# MessVerstaerker.net
KiCad netlist of a schematic drawn in EAGLE
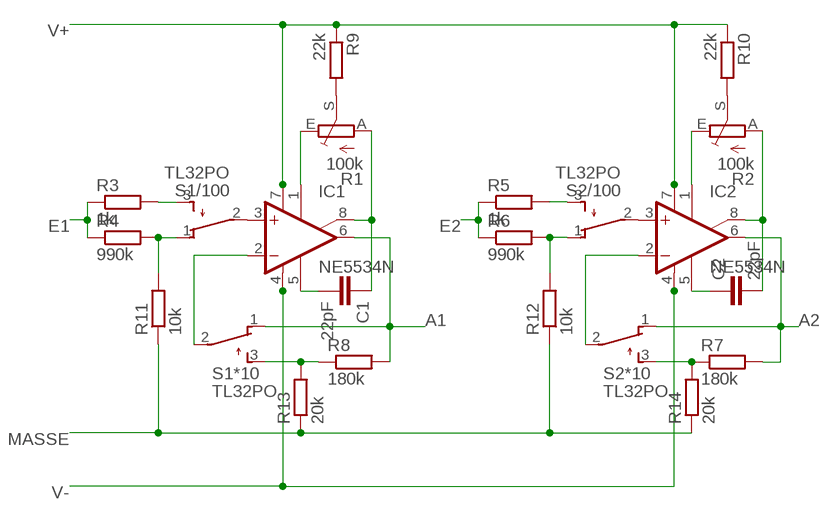
[diagram p0: schematic, sheet 1]

(export (version "E")
  (design (tool "Eeschema 10.0.6"))
  (components
    (comp (ref "C1")
      (value "22pF")
      (footprint "eagle-import:C2.5-2")
      (libsource (lib "eagle-import") (part "C2.5/2"))
    )
    (comp (ref "C2")
      (value "22pF")
      (footprint "eagle-import:C2.5-2")
      (libsource (lib "eagle-import") (part "C2.5/2"))
    )
    (comp (ref "IC1")
      (value "NE5534N")
      (footprint "eagle-import:DIL08")
      (libsource (lib "eagle-import") (part "NE5534N"))
    )
    (comp (ref "IC2")
      (value "NE5534N")
      (footprint "eagle-import:DIL08")
      (libsource (lib "eagle-import") (part "NE5534N"))
    )
    (comp (ref "R1")
      (value "100k")
      (footprint "eagle-import:B25V")
      (libsource (lib "eagle-import") (part "TRIM_EU-B25V"))
    )
    (comp (ref "R2")
      (value "100k")
      (footprint "eagle-import:B25V")
      (libsource (lib "eagle-import") (part "TRIM_EU-B25V"))
    )
    (comp (ref "R3")
      (value "1k")
      (footprint "eagle-import:0309_10")
      (libsource (lib "eagle-import") (part "R-EU_0309/10"))
    )
    (comp (ref "R4")
      (value "990k")
      (footprint "eagle-import:0309_10")
      (libsource (lib "eagle-import") (part "R-EU_0309/10"))
    )
    (comp (ref "R5")
      (value "1k")
      (footprint "eagle-import:0309_10")
      (libsource (lib "eagle-import") (part "R-EU_0309/10"))
    )
    (comp (ref "R6")
      (value "990k")
      (footprint "eagle-import:0309_10")
      (libsource (lib "eagle-import") (part "R-EU_0309/10"))
    )
    (comp (ref "R7")
      (value "180k")
      (footprint "eagle-import:0309_10")
      (libsource (lib "eagle-import") (part "R-EU_0309/10"))
    )
    (comp (ref "R8")
      (value "180k")
      (footprint "eagle-import:0309_10")
      (libsource (lib "eagle-import") (part "R-EU_0309/10"))
    )
    (comp (ref "R9")
      (value "22k")
      (footprint "eagle-import:0309_10")
      (libsource (lib "eagle-import") (part "R-EU_0309/10"))
    )
    (comp (ref "R10")
      (value "22k")
      (footprint "eagle-import:0309_10")
      (libsource (lib "eagle-import") (part "R-EU_0309/10"))
    )
    (comp (ref "R11")
      (value "10k")
      (footprint "eagle-import:0309_10")
      (libsource (lib "eagle-import") (part "R-EU_0309/10"))
    )
    (comp (ref "R12")
      (value "10k")
      (footprint "eagle-import:0309_10")
      (libsource (lib "eagle-import") (part "R-EU_0309/10"))
    )
    (comp (ref "R13")
      (value "20k")
      (footprint "eagle-import:0309_10")
      (libsource (lib "eagle-import") (part "R-EU_0309/10"))
    )
    (comp (ref "R14")
      (value "20k")
      (footprint "eagle-import:0309_10")
      (libsource (lib "eagle-import") (part "R-EU_0309/10"))
    )
    (comp (ref "S1*10")
      (value "TL32PO")
      (footprint "eagle-import:TL3XPO")
      (libsource (lib "eagle-import") (part "TL32PO"))
    )
    (comp (ref "S1/100")
      (value "TL32PO")
      (footprint "eagle-import:TL3XPO")
      (libsource (lib "eagle-import") (part "TL32PO"))
    )
    (comp (ref "S2*10")
      (value "TL32PO")
      (footprint "eagle-import:TL3XPO")
      (libsource (lib "eagle-import") (part "TL32PO"))
    )
    (comp (ref "S2/100")
      (value "TL32PO")
      (footprint "eagle-import:TL3XPO")
      (libsource (lib "eagle-import") (part "TL32PO"))
    )
  )
  (nets
    (net (code "1") (name "/A1") (class "Default")
      (node (ref "IC1") (pin "6") (pinfunction "OUT_6") (pintype "output"))
      (node (ref "R8") (pin "2") (pinfunction "2_2") (pintype "passive"))
      (node (ref "S1*10") (pin "1") (pinfunction "O_1") (pintype "passive"))
    )
    (net (code "2") (name "/A2") (class "Default")
      (node (ref "IC2") (pin "6") (pinfunction "OUT_6") (pintype "output"))
      (node (ref "R7") (pin "2") (pinfunction "2_2") (pintype "passive"))
      (node (ref "S2*10") (pin "1") (pinfunction "O_1") (pintype "passive"))
    )
    (net (code "3") (name "/E1") (class "Default")
      (node (ref "R3") (pin "1") (pinfunction "1_1") (pintype "passive"))
      (node (ref "R4") (pin "1") (pinfunction "1_1") (pintype "passive"))
    )
    (net (code "4") (name "/E2") (class "Default")
      (node (ref "R5") (pin "1") (pinfunction "1_1") (pintype "passive"))
      (node (ref "R6") (pin "1") (pinfunction "1_1") (pintype "passive"))
    )
    (net (code "5") (name "/MASSE") (class "Default")
      (node (ref "R11") (pin "1") (pinfunction "1_1") (pintype "passive"))
      (node (ref "R12") (pin "1") (pinfunction "1_1") (pintype "passive"))
      (node (ref "R13") (pin "1") (pinfunction "1_1") (pintype "passive"))
      (node (ref "R14") (pin "1") (pinfunction "1_1") (pintype "passive"))
    )
    (net (code "6") (name "/V+") (class "Default")
      (node (ref "IC1") (pin "7") (pinfunction "V+_7") (pintype "power_in"))
      (node (ref "IC2") (pin "7") (pinfunction "V+_7") (pintype "power_in"))
      (node (ref "R10") (pin "1") (pinfunction "1_1") (pintype "passive"))
      (node (ref "R9") (pin "1") (pinfunction "1_1") (pintype "passive"))
    )
    (net (code "7") (name "/V-") (class "Default")
      (node (ref "IC1") (pin "4") (pinfunction "V-_4") (pintype "power_in"))
      (node (ref "IC2") (pin "4") (pinfunction "V-_4") (pintype "power_in"))
    )
    (net (code "8") (name "Net-(IC1-+IN)") (class "Default")
      (node (ref "IC1") (pin "3") (pinfunction "+IN_3") (pintype "input"))
      (node (ref "S1/100") (pin "2") (pinfunction "P_2") (pintype "passive"))
    )
    (net (code "9") (name "Net-(IC1--IN)") (class "Default")
      (node (ref "IC1") (pin "2") (pinfunction "-IN_2") (pintype "input"))
      (node (ref "S1*10") (pin "2") (pinfunction "P_2") (pintype "passive"))
    )
    (net (code "10") (name "Net-(IC1-CMP)") (class "Default")
      (node (ref "C1") (pin "2") (pinfunction "2_2") (pintype "passive"))
      (node (ref "IC1") (pin "5") (pinfunction "CMP_5") (pintype "passive"))
    )
    (net (code "11") (name "Net-(IC1-ON)") (class "Default")
      (node (ref "IC1") (pin "1") (pinfunction "ON_1") (pintype "passive"))
      (node (ref "R1") (pin "E") (pinfunction "E_E") (pintype "passive"))
    )
    (net (code "12") (name "Net-(IC1-ON{slash}CMP)") (class "Default")
      (node (ref "C1") (pin "1") (pinfunction "1_1") (pintype "passive"))
      (node (ref "IC1") (pin "8") (pinfunction "ON/CMP_8") (pintype "passive"))
      (node (ref "R1") (pin "A") (pinfunction "A_A") (pintype "passive"))
    )
    (net (code "13") (name "Net-(IC2-+IN)") (class "Default")
      (node (ref "IC2") (pin "3") (pinfunction "+IN_3") (pintype "input"))
      (node (ref "S2/100") (pin "2") (pinfunction "P_2") (pintype "passive"))
    )
    (net (code "14") (name "Net-(IC2--IN)") (class "Default")
      (node (ref "IC2") (pin "2") (pinfunction "-IN_2") (pintype "input"))
      (node (ref "S2*10") (pin "2") (pinfunction "P_2") (pintype "passive"))
    )
    (net (code "15") (name "Net-(IC2-CMP)") (class "Default")
      (node (ref "C2") (pin "1") (pinfunction "1_1") (pintype "passive"))
      (node (ref "IC2") (pin "5") (pinfunction "CMP_5") (pintype "passive"))
    )
    (net (code "16") (name "Net-(IC2-ON)") (class "Default")
      (node (ref "IC2") (pin "1") (pinfunction "ON_1") (pintype "passive"))
      (node (ref "R2") (pin "E") (pinfunction "E_E") (pintype "passive"))
    )
    (net (code "17") (name "Net-(IC2-ON{slash}CMP)") (class "Default")
      (node (ref "C2") (pin "2") (pinfunction "2_2") (pintype "passive"))
      (node (ref "IC2") (pin "8") (pinfunction "ON/CMP_8") (pintype "passive"))
      (node (ref "R2") (pin "A") (pinfunction "A_A") (pintype "passive"))
    )
    (net (code "18") (name "Net-(R1-PadS)") (class "Default")
      (node (ref "R1") (pin "S") (pinfunction "S_S") (pintype "passive"))
      (node (ref "R9") (pin "2") (pinfunction "2_2") (pintype "passive"))
    )
    (net (code "19") (name "Net-(R10-Pad2)") (class "Default")
      (node (ref "R10") (pin "2") (pinfunction "2_2") (pintype "passive"))
      (node (ref "R2") (pin "S") (pinfunction "S_S") (pintype "passive"))
    )
    (net (code "20") (name "Net-(S1*10-S)") (class "Default")
      (node (ref "R13") (pin "2") (pinfunction "2_2") (pintype "passive"))
      (node (ref "R8") (pin "1") (pinfunction "1_1") (pintype "passive"))
      (node (ref "S1*10") (pin "3") (pinfunction "S_3") (pintype "passive"))
    )
    (net (code "21") (name "Net-(S1/100-O)") (class "Default")
      (node (ref "R11") (pin "2") (pinfunction "2_2") (pintype "passive"))
      (node (ref "R4") (pin "2") (pinfunction "2_2") (pintype "passive"))
      (node (ref "S1/100") (pin "1") (pinfunction "O_1") (pintype "passive"))
    )
    (net (code "22") (name "Net-(S1/100-S)") (class "Default")
      (node (ref "R3") (pin "2") (pinfunction "2_2") (pintype "passive"))
      (node (ref "S1/100") (pin "3") (pinfunction "S_3") (pintype "passive"))
    )
    (net (code "23") (name "Net-(S2*10-S)") (class "Default")
      (node (ref "R14") (pin "2") (pinfunction "2_2") (pintype "passive"))
      (node (ref "R7") (pin "1") (pinfunction "1_1") (pintype "passive"))
      (node (ref "S2*10") (pin "3") (pinfunction "S_3") (pintype "passive"))
    )
    (net (code "24") (name "Net-(S2/100-O)") (class "Default")
      (node (ref "R12") (pin "2") (pinfunction "2_2") (pintype "passive"))
      (node (ref "R6") (pin "2") (pinfunction "2_2") (pintype "passive"))
      (node (ref "S2/100") (pin "1") (pinfunction "O_1") (pintype "passive"))
    )
    (net (code "25") (name "Net-(S2/100-S)") (class "Default")
      (node (ref "R5") (pin "2") (pinfunction "2_2") (pintype "passive"))
      (node (ref "S2/100") (pin "3") (pinfunction "S_3") (pintype "passive"))
    )
  )
)
